# power.net
KiCad netlist of a schematic drawn in Altium Designer
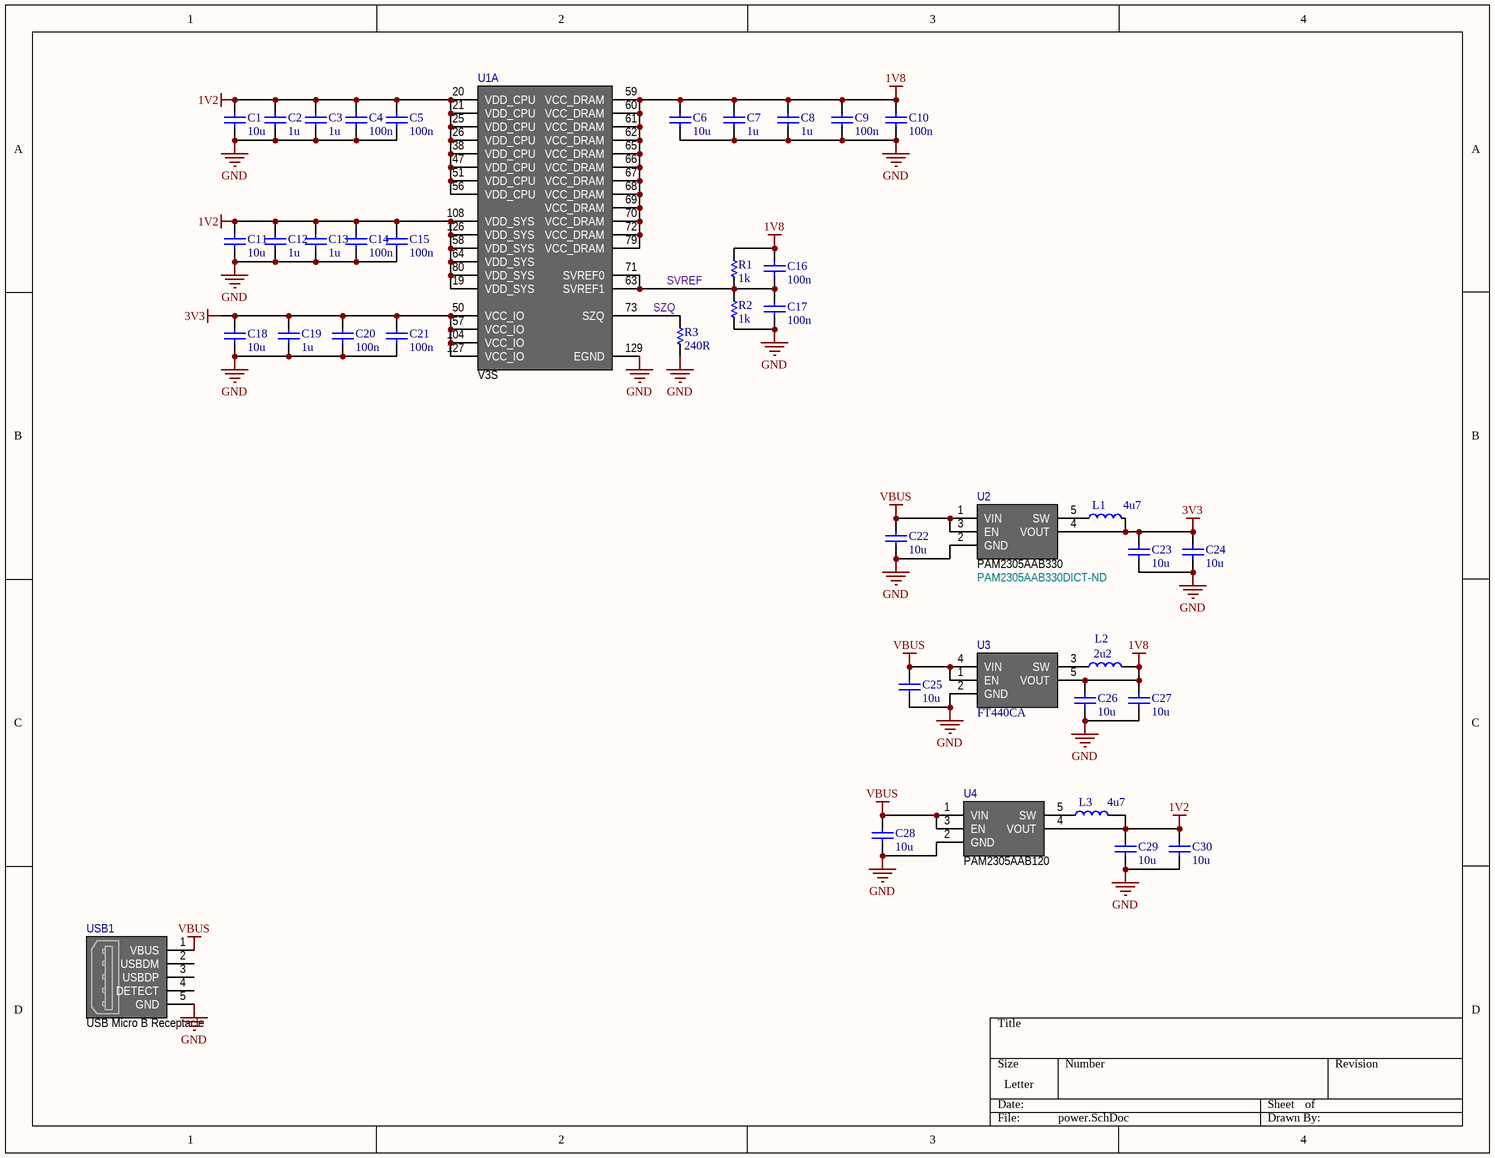
[diagram p0: power.SchDoc]

(export (version "E")
  (design (tool "Eeschema 10.0.6"))
  (components
    (comp (ref "C1")
      (value "10u")
      (footprint "CAPC1608N")
      (description "Capacitor (Semiconductor SIM Model)")
      (fields (field (name "PUBLISHER") "Altium Limited"))
      (libsource (lib "Miscellaneous Devices") (part "Cap Semi"))
    )
    (comp (ref "C2")
      (value "1u")
      (footprint "CAPC1005N")
      (description "Capacitor (Semiconductor SIM Model)")
      (fields (field (name "PUBLISHER") "Altium Limited"))
      (libsource (lib "Miscellaneous Devices") (part "Cap Semi"))
    )
    (comp (ref "C3")
      (value "1u")
      (footprint "CAPC1005N")
      (description "Capacitor (Semiconductor SIM Model)")
      (fields (field (name "PUBLISHER") "Altium Limited"))
      (libsource (lib "Miscellaneous Devices") (part "Cap Semi"))
    )
    (comp (ref "C4")
      (value "100n")
      (footprint "CAPC1005N")
      (description "Capacitor (Semiconductor SIM Model)")
      (fields (field (name "PUBLISHER") "Altium Limited"))
      (libsource (lib "Miscellaneous Devices") (part "Cap Semi"))
    )
    (comp (ref "C5")
      (value "100n")
      (footprint "CAPC1005N")
      (description "Capacitor (Semiconductor SIM Model)")
      (fields (field (name "PUBLISHER") "Altium Limited"))
      (libsource (lib "Miscellaneous Devices") (part "Cap Semi"))
    )
    (comp (ref "C6")
      (value "10u")
      (footprint "CAPC1608N")
      (description "Capacitor (Semiconductor SIM Model)")
      (fields (field (name "PUBLISHER") "Altium Limited"))
      (libsource (lib "Miscellaneous Devices") (part "Cap Semi"))
    )
    (comp (ref "C7")
      (value "1u")
      (footprint "CAPC1005N")
      (description "Capacitor (Semiconductor SIM Model)")
      (fields (field (name "PUBLISHER") "Altium Limited"))
      (libsource (lib "Miscellaneous Devices") (part "Cap Semi"))
    )
    (comp (ref "C8")
      (value "1u")
      (footprint "CAPC1005N")
      (description "Capacitor (Semiconductor SIM Model)")
      (fields (field (name "PUBLISHER") "Altium Limited"))
      (libsource (lib "Miscellaneous Devices") (part "Cap Semi"))
    )
    (comp (ref "C9")
      (value "100n")
      (footprint "CAPC1005N")
      (description "Capacitor (Semiconductor SIM Model)")
      (fields (field (name "PUBLISHER") "Altium Limited"))
      (libsource (lib "Miscellaneous Devices") (part "Cap Semi"))
    )
    (comp (ref "C10")
      (value "100n")
      (footprint "CAPC1005N")
      (description "Capacitor (Semiconductor SIM Model)")
      (fields (field (name "PUBLISHER") "Altium Limited"))
      (libsource (lib "Miscellaneous Devices") (part "Cap Semi"))
    )
    (comp (ref "C11")
      (value "10u")
      (footprint "CAPC1608N")
      (description "Capacitor (Semiconductor SIM Model)")
      (fields (field (name "PUBLISHER") "Altium Limited"))
      (libsource (lib "Miscellaneous Devices") (part "Cap Semi"))
    )
    (comp (ref "C12")
      (value "1u")
      (footprint "CAPC1005N")
      (description "Capacitor (Semiconductor SIM Model)")
      (fields (field (name "PUBLISHER") "Altium Limited"))
      (libsource (lib "Miscellaneous Devices") (part "Cap Semi"))
    )
    (comp (ref "C13")
      (value "1u")
      (footprint "CAPC1005N")
      (description "Capacitor (Semiconductor SIM Model)")
      (fields (field (name "PUBLISHER") "Altium Limited"))
      (libsource (lib "Miscellaneous Devices") (part "Cap Semi"))
    )
    (comp (ref "C14")
      (value "100n")
      (footprint "CAPC1005N")
      (description "Capacitor (Semiconductor SIM Model)")
      (fields (field (name "PUBLISHER") "Altium Limited"))
      (libsource (lib "Miscellaneous Devices") (part "Cap Semi"))
    )
    (comp (ref "C15")
      (value "100n")
      (footprint "CAPC1005N")
      (description "Capacitor (Semiconductor SIM Model)")
      (fields (field (name "PUBLISHER") "Altium Limited"))
      (libsource (lib "Miscellaneous Devices") (part "Cap Semi"))
    )
    (comp (ref "C16")
      (value "100n")
      (footprint "CAPC1005N")
      (description "Capacitor (Semiconductor SIM Model)")
      (fields (field (name "PUBLISHER") "Altium Limited"))
      (libsource (lib "Miscellaneous Devices") (part "Cap Semi"))
    )
    (comp (ref "C17")
      (value "100n")
      (footprint "CAPC1005N")
      (description "Capacitor (Semiconductor SIM Model)")
      (fields (field (name "PUBLISHER") "Altium Limited"))
      (libsource (lib "Miscellaneous Devices") (part "Cap Semi"))
    )
    (comp (ref "C18")
      (value "10u")
      (footprint "CAPC1608N")
      (description "Capacitor (Semiconductor SIM Model)")
      (fields (field (name "PUBLISHER") "Altium Limited"))
      (libsource (lib "Miscellaneous Devices") (part "Cap Semi"))
    )
    (comp (ref "C19")
      (value "1u")
      (footprint "CAPC1005N")
      (description "Capacitor (Semiconductor SIM Model)")
      (fields (field (name "PUBLISHER") "Altium Limited"))
      (libsource (lib "Miscellaneous Devices") (part "Cap Semi"))
    )
    (comp (ref "C20")
      (value "100n")
      (footprint "CAPC1005N")
      (description "Capacitor (Semiconductor SIM Model)")
      (fields (field (name "PUBLISHER") "Altium Limited"))
      (libsource (lib "Miscellaneous Devices") (part "Cap Semi"))
    )
    (comp (ref "C21")
      (value "100n")
      (footprint "CAPC1005N")
      (description "Capacitor (Semiconductor SIM Model)")
      (fields (field (name "PUBLISHER") "Altium Limited"))
      (libsource (lib "Miscellaneous Devices") (part "Cap Semi"))
    )
    (comp (ref "C22")
      (value "10u")
      (footprint "CAPC1608N")
      (description "Capacitor (Semiconductor SIM Model)")
      (fields (field (name "PUBLISHER") "Altium Limited"))
      (libsource (lib "Miscellaneous Devices") (part "Cap Semi"))
    )
    (comp (ref "C23")
      (value "10u")
      (footprint "CAPC1608N")
      (description "Capacitor (Semiconductor SIM Model)")
      (fields (field (name "PUBLISHER") "Altium Limited"))
      (libsource (lib "Miscellaneous Devices") (part "Cap Semi"))
    )
    (comp (ref "C24")
      (value "10u")
      (footprint "CAPC1608N")
      (description "Capacitor (Semiconductor SIM Model)")
      (fields (field (name "PUBLISHER") "Altium Limited"))
      (libsource (lib "Miscellaneous Devices") (part "Cap Semi"))
    )
    (comp (ref "C25")
      (value "10u")
      (footprint "CAPC1608N")
      (description "Capacitor (Semiconductor SIM Model)")
      (fields (field (name "PUBLISHER") "Altium Limited"))
      (libsource (lib "Miscellaneous Devices") (part "Cap Semi"))
    )
    (comp (ref "C26")
      (value "10u")
      (footprint "CAPC1608N")
      (description "Capacitor (Semiconductor SIM Model)")
      (fields (field (name "PUBLISHER") "Altium Limited"))
      (libsource (lib "Miscellaneous Devices") (part "Cap Semi"))
    )
    (comp (ref "C27")
      (value "10u")
      (footprint "CAPC1608N")
      (description "Capacitor (Semiconductor SIM Model)")
      (fields (field (name "PUBLISHER") "Altium Limited"))
      (libsource (lib "Miscellaneous Devices") (part "Cap Semi"))
    )
    (comp (ref "C28")
      (value "10u")
      (footprint "CAPC1608N")
      (description "Capacitor (Semiconductor SIM Model)")
      (fields (field (name "PUBLISHER") "Altium Limited"))
      (libsource (lib "Miscellaneous Devices") (part "Cap Semi"))
    )
    (comp (ref "C29")
      (value "10u")
      (footprint "CAPC1608N")
      (description "Capacitor (Semiconductor SIM Model)")
      (fields (field (name "PUBLISHER") "Altium Limited"))
      (libsource (lib "Miscellaneous Devices") (part "Cap Semi"))
    )
    (comp (ref "C30")
      (value "10u")
      (footprint "CAPC1608N")
      (description "Capacitor (Semiconductor SIM Model)")
      (fields (field (name "PUBLISHER") "Altium Limited"))
      (libsource (lib "Miscellaneous Devices") (part "Cap Semi"))
    )
    (comp (ref "L1")
      (value "4u7")
      (footprint "INDC2520X12N")
      (description "Inductor")
      (fields (field (name "PUBLISHER") "Altium Limited"))
      (libsource (lib "Miscellaneous Devices") (part "Inductor"))
    )
    (comp (ref "L2")
      (value "2u2")
      (footprint "INDC2520X12N")
      (description "Inductor")
      (fields (field (name "PUBLISHER") "Altium Limited"))
      (libsource (lib "Miscellaneous Devices") (part "Inductor"))
    )
    (comp (ref "L3")
      (value "4u7")
      (footprint "INDC2520X12N")
      (description "Inductor")
      (fields (field (name "PUBLISHER") "Altium Limited"))
      (libsource (lib "Miscellaneous Devices") (part "Inductor"))
    )
    (comp (ref "R1")
      (value "1k")
      (footprint "RESC1005N")
      (description "Semiconductor Resistor")
      (fields (field (name "PUBLISHER") "Altium Limited"))
      (libsource (lib "Miscellaneous Devices") (part "Res Semi"))
    )
    (comp (ref "R2")
      (value "1k")
      (footprint "RESC1005N")
      (description "Semiconductor Resistor")
      (fields (field (name "PUBLISHER") "Altium Limited"))
      (libsource (lib "Miscellaneous Devices") (part "Res Semi"))
    )
    (comp (ref "R3")
      (value "240R")
      (footprint "RESC1005N")
      (description "Semiconductor Resistor")
      (fields (field (name "PUBLISHER") "Altium Limited"))
      (libsource (lib "Miscellaneous Devices") (part "Res Semi"))
    )
    (comp (ref "U1") (value "V3S") (footprint "V3S") (libsource (lib "Allwinner SoC") (part "V3S")))
    (comp (ref "U2")
      (value "PAM2305AAB330")
      (footprint "TSOT25-5N")
      (description "IC REG BUCK 3.3V 1A SYNC TSOT25")
      (fields
        (field (name "MANUFACTURER") "Diodes Incorporated")
        (field (name "SUPPLIER PART NUMBER 1") "PAM2305AAB330DICT-ND")
      )
      (libsource (lib "Diodes Inc Switching Regulator") (part "PAM2305AAB330"))
    )
    (comp (ref "U3")
      (value "FT440CA")
      (footprint "SOT23-5AN")
      (description "IC REG BUCK 1.8V 0.6A SYNC SOT23")
      (fields (field (name "MANUFACTURER") "Fremont Micro Devices USA"))
      (libsource (lib "FMD DC-DC Converter") (part "FT440CA"))
    )
    (comp (ref "U4")
      (value "PAM2305AAB120")
      (footprint "TSOT25-5N")
      (description "IC REG BUCK 1.2V 1A SYNC TSOT25")
      (fields (field (name "MANUFACTURER") "Diodes Incorporated"))
      (libsource (lib "Diodes Inc Switching Regulator") (part "PAM2305AAB120"))
    )
    (comp (ref "USB1")
      (value "USB Micro B Receptacle")
      (footprint "10118193-0001LF")
      (libsource (lib "Miscellaneous Connectors") (part "USB Micro B Receptacle"))
    )
  )
  (nets
    (net (code "1") (name "/SVREF") (class "Default")
      (node (ref "C16") (pin "1") (pinfunction "1_1") (pintype "passive"))
      (node (ref "C17") (pin "2") (pinfunction "2_2") (pintype "passive"))
      (node (ref "R1") (pin "1") (pinfunction "1_1") (pintype "passive"))
      (node (ref "R2") (pin "2") (pinfunction "2_2") (pintype "passive"))
      (node (ref "U1") (pin "63") (pinfunction "SVREF1_63") (pintype "passive"))
      (node (ref "U1") (pin "71") (pinfunction "SVREF0_71") (pintype "passive"))
    )
    (net (code "2") (name "/SZQ") (class "Default")
      (node (ref "R3") (pin "2") (pinfunction "2_2") (pintype "passive"))
      (node (ref "U1") (pin "73") (pinfunction "SZQ_73") (pintype "passive"))
    )
    (net (code "3") (name "1V2") (class "Default")
      (node (ref "C1") (pin "2") (pinfunction "2_2") (pintype "passive"))
      (node (ref "C11") (pin "2") (pinfunction "2_2") (pintype "passive"))
      (node (ref "C12") (pin "2") (pinfunction "2_2") (pintype "passive"))
      (node (ref "C13") (pin "2") (pinfunction "2_2") (pintype "passive"))
      (node (ref "C14") (pin "2") (pinfunction "2_2") (pintype "passive"))
      (node (ref "C15") (pin "2") (pinfunction "2_2") (pintype "passive"))
      (node (ref "C2") (pin "2") (pinfunction "2_2") (pintype "passive"))
      (node (ref "C29") (pin "2") (pinfunction "2_2") (pintype "passive"))
      (node (ref "C3") (pin "2") (pinfunction "2_2") (pintype "passive"))
      (node (ref "C30") (pin "2") (pinfunction "2_2") (pintype "passive"))
      (node (ref "C4") (pin "2") (pinfunction "2_2") (pintype "passive"))
      (node (ref "C5") (pin "2") (pinfunction "2_2") (pintype "passive"))
      (node (ref "L3") (pin "2") (pinfunction "2_2") (pintype "passive"))
      (node (ref "U1") (pin "108") (pinfunction "VDD_SYS_108") (pintype "passive"))
      (node (ref "U1") (pin "126") (pinfunction "VDD_SYS_126") (pintype "passive"))
      (node (ref "U1") (pin "19") (pinfunction "VDD_SYS_19") (pintype "passive"))
      (node (ref "U1") (pin "20") (pinfunction "VDD_CPU_20") (pintype "passive"))
      (node (ref "U1") (pin "21") (pinfunction "VDD_CPU_21") (pintype "passive"))
      (node (ref "U1") (pin "25") (pinfunction "VDD_CPU_25") (pintype "passive"))
      (node (ref "U1") (pin "26") (pinfunction "VDD_CPU_26") (pintype "passive"))
      (node (ref "U1") (pin "38") (pinfunction "VDD_CPU_38") (pintype "passive"))
      (node (ref "U1") (pin "47") (pinfunction "VDD_CPU_47") (pintype "passive"))
      (node (ref "U1") (pin "51") (pinfunction "VDD_CPU_51") (pintype "passive"))
      (node (ref "U1") (pin "56") (pinfunction "VDD_CPU_56") (pintype "passive"))
      (node (ref "U1") (pin "58") (pinfunction "VDD_SYS_58") (pintype "passive"))
      (node (ref "U1") (pin "64") (pinfunction "VDD_SYS_64") (pintype "passive"))
      (node (ref "U1") (pin "80") (pinfunction "VDD_SYS_80") (pintype "passive"))
      (node (ref "U4") (pin "4") (pinfunction "VOUT_4") (pintype "passive"))
    )
    (net (code "4") (name "1V8") (class "Default")
      (node (ref "C10") (pin "2") (pinfunction "2_2") (pintype "passive"))
      (node (ref "C16") (pin "2") (pinfunction "2_2") (pintype "passive"))
      (node (ref "C26") (pin "2") (pinfunction "2_2") (pintype "passive"))
      (node (ref "C27") (pin "2") (pinfunction "2_2") (pintype "passive"))
      (node (ref "C6") (pin "2") (pinfunction "2_2") (pintype "passive"))
      (node (ref "C7") (pin "2") (pinfunction "2_2") (pintype "passive"))
      (node (ref "C8") (pin "2") (pinfunction "2_2") (pintype "passive"))
      (node (ref "C9") (pin "2") (pinfunction "2_2") (pintype "passive"))
      (node (ref "L2") (pin "2") (pinfunction "2_2") (pintype "passive"))
      (node (ref "R1") (pin "2") (pinfunction "2_2") (pintype "passive"))
      (node (ref "U1") (pin "59") (pinfunction "VCC_DRAM_59") (pintype "passive"))
      (node (ref "U1") (pin "60") (pinfunction "VCC_DRAM_60") (pintype "passive"))
      (node (ref "U1") (pin "61") (pinfunction "VCC_DRAM_61") (pintype "passive"))
      (node (ref "U1") (pin "62") (pinfunction "VCC_DRAM_62") (pintype "passive"))
      (node (ref "U1") (pin "65") (pinfunction "VCC_DRAM_65") (pintype "passive"))
      (node (ref "U1") (pin "66") (pinfunction "VCC_DRAM_66") (pintype "passive"))
      (node (ref "U1") (pin "67") (pinfunction "VCC_DRAM_67") (pintype "passive"))
      (node (ref "U1") (pin "68") (pinfunction "VCC_DRAM_68") (pintype "passive"))
      (node (ref "U1") (pin "69") (pinfunction "VCC_DRAM_69") (pintype "passive"))
      (node (ref "U1") (pin "70") (pinfunction "VCC_DRAM_70") (pintype "passive"))
      (node (ref "U1") (pin "72") (pinfunction "VCC_DRAM_72") (pintype "passive"))
      (node (ref "U1") (pin "79") (pinfunction "VCC_DRAM_79") (pintype "passive"))
      (node (ref "U3") (pin "5") (pinfunction "VOUT_5") (pintype "power_in"))
    )
    (net (code "5") (name "3V3") (class "Default")
      (node (ref "C18") (pin "2") (pinfunction "2_2") (pintype "passive"))
      (node (ref "C19") (pin "2") (pinfunction "2_2") (pintype "passive"))
      (node (ref "C20") (pin "2") (pinfunction "2_2") (pintype "passive"))
      (node (ref "C21") (pin "2") (pinfunction "2_2") (pintype "passive"))
      (node (ref "C23") (pin "2") (pinfunction "2_2") (pintype "passive"))
      (node (ref "C24") (pin "2") (pinfunction "2_2") (pintype "passive"))
      (node (ref "L1") (pin "2") (pinfunction "2_2") (pintype "passive"))
      (node (ref "U1") (pin "104") (pinfunction "VCC_IO_104") (pintype "passive"))
      (node (ref "U1") (pin "127") (pinfunction "VCC_IO_127") (pintype "passive"))
      (node (ref "U1") (pin "50") (pinfunction "VCC_IO_50") (pintype "passive"))
      (node (ref "U1") (pin "57") (pinfunction "VCC_IO_57") (pintype "passive"))
      (node (ref "U2") (pin "4") (pinfunction "VOUT_4") (pintype "passive"))
    )
    (net (code "6") (name "GND") (class "Default")
      (node (ref "C1") (pin "1") (pinfunction "1_1") (pintype "passive"))
      (node (ref "C10") (pin "1") (pinfunction "1_1") (pintype "passive"))
      (node (ref "C11") (pin "1") (pinfunction "1_1") (pintype "passive"))
      (node (ref "C12") (pin "1") (pinfunction "1_1") (pintype "passive"))
      (node (ref "C13") (pin "1") (pinfunction "1_1") (pintype "passive"))
      (node (ref "C14") (pin "1") (pinfunction "1_1") (pintype "passive"))
      (node (ref "C15") (pin "1") (pinfunction "1_1") (pintype "passive"))
      (node (ref "C17") (pin "1") (pinfunction "1_1") (pintype "passive"))
      (node (ref "C18") (pin "1") (pinfunction "1_1") (pintype "passive"))
      (node (ref "C19") (pin "1") (pinfunction "1_1") (pintype "passive"))
      (node (ref "C2") (pin "1") (pinfunction "1_1") (pintype "passive"))
      (node (ref "C20") (pin "1") (pinfunction "1_1") (pintype "passive"))
      (node (ref "C21") (pin "1") (pinfunction "1_1") (pintype "passive"))
      (node (ref "C22") (pin "1") (pinfunction "1_1") (pintype "passive"))
      (node (ref "C23") (pin "1") (pinfunction "1_1") (pintype "passive"))
      (node (ref "C24") (pin "1") (pinfunction "1_1") (pintype "passive"))
      (node (ref "C25") (pin "1") (pinfunction "1_1") (pintype "passive"))
      (node (ref "C26") (pin "1") (pinfunction "1_1") (pintype "passive"))
      (node (ref "C27") (pin "1") (pinfunction "1_1") (pintype "passive"))
      (node (ref "C28") (pin "1") (pinfunction "1_1") (pintype "passive"))
      (node (ref "C29") (pin "1") (pinfunction "1_1") (pintype "passive"))
      (node (ref "C3") (pin "1") (pinfunction "1_1") (pintype "passive"))
      (node (ref "C30") (pin "1") (pinfunction "1_1") (pintype "passive"))
      (node (ref "C4") (pin "1") (pinfunction "1_1") (pintype "passive"))
      (node (ref "C5") (pin "1") (pinfunction "1_1") (pintype "passive"))
      (node (ref "C6") (pin "1") (pinfunction "1_1") (pintype "passive"))
      (node (ref "C7") (pin "1") (pinfunction "1_1") (pintype "passive"))
      (node (ref "C8") (pin "1") (pinfunction "1_1") (pintype "passive"))
      (node (ref "C9") (pin "1") (pinfunction "1_1") (pintype "passive"))
      (node (ref "R2") (pin "1") (pinfunction "1_1") (pintype "passive"))
      (node (ref "R3") (pin "1") (pinfunction "1_1") (pintype "passive"))
      (node (ref "U1") (pin "129") (pinfunction "EGND_129") (pintype "passive"))
      (node (ref "U2") (pin "2") (pinfunction "GND_2") (pintype "passive"))
      (node (ref "U3") (pin "2") (pinfunction "GND_2") (pintype "power_in"))
      (node (ref "U4") (pin "2") (pinfunction "GND_2") (pintype "passive"))
      (node (ref "USB1") (pin "5") (pinfunction "GND_5") (pintype "power_in"))
    )
    (net (code "7") (name "Net-(U2-SW)") (class "Default")
      (node (ref "L1") (pin "1") (pinfunction "1_1") (pintype "passive"))
      (node (ref "U2") (pin "5") (pinfunction "SW_5") (pintype "passive"))
    )
    (net (code "8") (name "Net-(U3-SW)") (class "Default")
      (node (ref "L2") (pin "1") (pinfunction "1_1") (pintype "passive"))
      (node (ref "U3") (pin "3") (pinfunction "SW_3") (pintype "power_in"))
    )
    (net (code "9") (name "Net-(U4-SW)") (class "Default")
      (node (ref "L3") (pin "1") (pinfunction "1_1") (pintype "passive"))
      (node (ref "U4") (pin "5") (pinfunction "SW_5") (pintype "passive"))
    )
    (net (code "10") (name "VBUS") (class "Default")
      (node (ref "C22") (pin "2") (pinfunction "2_2") (pintype "passive"))
      (node (ref "C25") (pin "2") (pinfunction "2_2") (pintype "passive"))
      (node (ref "C28") (pin "2") (pinfunction "2_2") (pintype "passive"))
      (node (ref "U2") (pin "1") (pinfunction "VIN_1") (pintype "passive"))
      (node (ref "U2") (pin "3") (pinfunction "EN_3") (pintype "passive"))
      (node (ref "U3") (pin "1") (pinfunction "EN_1") (pintype "power_in"))
      (node (ref "U3") (pin "4") (pinfunction "VIN_4") (pintype "power_in"))
      (node (ref "U4") (pin "1") (pinfunction "VIN_1") (pintype "passive"))
      (node (ref "U4") (pin "3") (pinfunction "EN_3") (pintype "passive"))
      (node (ref "USB1") (pin "1") (pinfunction "VBUS_1") (pintype "power_in"))
    )
    (net (code "11") (name "unconnected-(USB1-DETECT-Pad4)") (class "Default")
      (node (ref "USB1") (pin "4") (pinfunction "DETECT_4") (pintype "power_in"))
    )
    (net (code "12") (name "unconnected-(USB1-USBDM-Pad2)") (class "Default")
      (node (ref "USB1") (pin "2") (pinfunction "USBDM_2") (pintype "power_in"))
    )
    (net (code "13") (name "unconnected-(USB1-USBDP-Pad3)") (class "Default")
      (node (ref "USB1") (pin "3") (pinfunction "USBDP_3") (pintype "power_in"))
    )
  )
)
